# 04_-_CPU_SIGNALS.net
KiCad netlist of a schematic drawn in Altium Designer
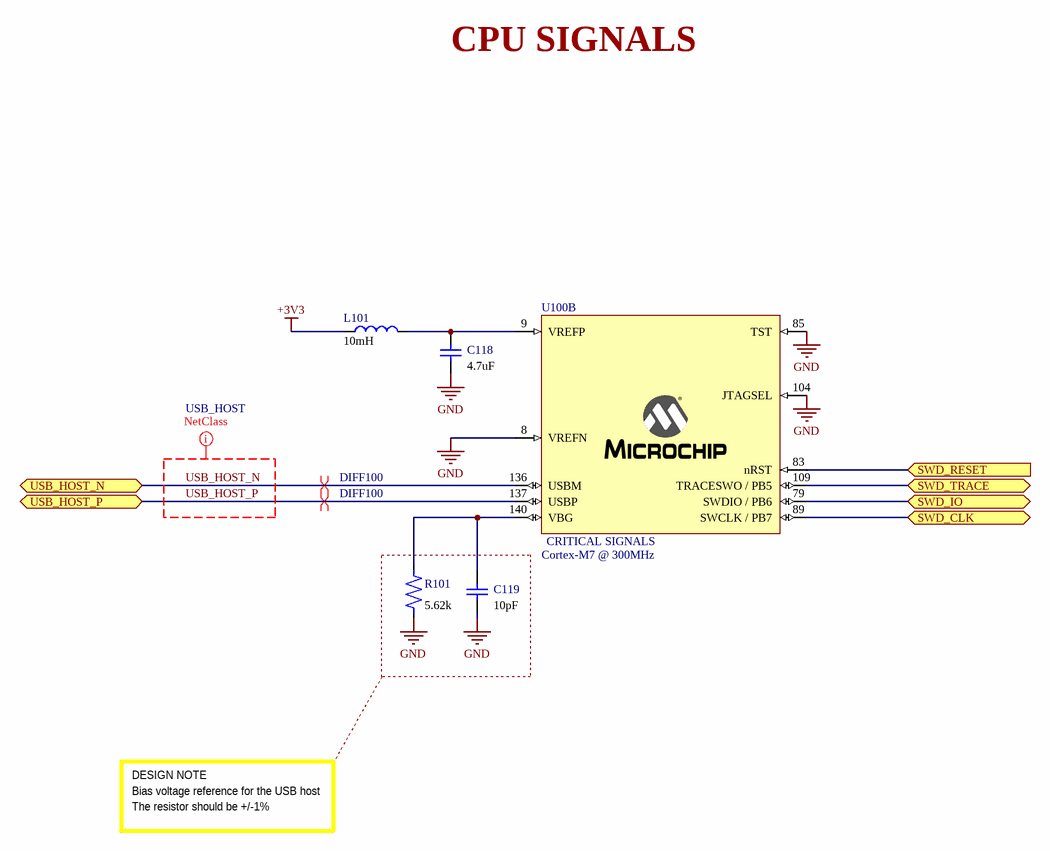
[diagram p0: [04] - CPU SIGNALS.SchDoc]

(export (version "E")
  (design (tool "Eeschema 10.0.6"))
  (components
    (comp (ref "C118")
      (value "4.7uF")
      (footprint "C0402")
      (description "C0402")
      (fields (field (name "Comment") "04023C103KAT2A"))
      (libsource (lib "Passive components") (part "04023C103KAT2A"))
    )
    (comp (ref "C119")
      (value "10pF")
      (footprint "C0402")
      (description "C0402")
      (fields (field (name "Comment") "04023C103KAT2A"))
      (libsource (lib "Passive components") (part "04023C103KAT2A"))
    )
    (comp (ref "L101")
      (value "10mH")
      (footprint "Inductor 0603")
      (description "Inductor 0603")
      (fields (field (name "Comment") "MLZ1608A2R2WT"))
      (libsource (lib "Passive components") (part "MLZ1608A2R2WT"))
    )
    (comp (ref "R101")
      (value "5.62k")
      (footprint "R0402")
      (description "R0402")
      (fields (field (name "Comment") "CRCW04020000Z0ED"))
      (libsource (lib "Passive components") (part "CRCW04020000Z0ED"))
    )
    (comp (ref "U100")
      (value "Cortex-M7 @ 300MHz")
      (footprint "ATSAMS70Q21A-AN")
      (description "ATSAMS70Q21")
      (libsource (lib "Microcontrollers") (part "ATSAMS70Q21A-AN"))
    )
  )
  (nets
    (net (code "1") (name "+3V3") (class "Default")
      (node (ref "L101") (pin "1") (pinfunction "1_1") (pintype "passive"))
    )
    (net (code "2") (name "/SWD_CLK") (class "Default")
      (node (ref "U100") (pin "89") (pinfunction "SWCLK_/_PB7_89") (pintype "bidirectional"))
    )
    (net (code "3") (name "/SWD_IO") (class "Default")
      (node (ref "U100") (pin "79") (pinfunction "SWDIO_/_PB6_79") (pintype "bidirectional"))
    )
    (net (code "4") (name "/SWD_RESET") (class "Default")
      (node (ref "U100") (pin "83") (pinfunction "nRST_83") (pintype "input"))
    )
    (net (code "5") (name "/SWD_TRACE") (class "Default")
      (node (ref "U100") (pin "109") (pinfunction "TRACESWO_/_PB5_109") (pintype "bidirectional"))
    )
    (net (code "6") (name "/USB_HOST_N") (class "Default")
      (node (ref "U100") (pin "136") (pinfunction "USBM_136") (pintype "bidirectional"))
    )
    (net (code "7") (name "/USB_HOST_P") (class "Default")
      (node (ref "U100") (pin "137") (pinfunction "USBP_137") (pintype "bidirectional"))
    )
    (net (code "8") (name "GND") (class "Default")
      (node (ref "C118") (pin "1") (pinfunction "1_1") (pintype "passive"))
      (node (ref "C119") (pin "1") (pinfunction "1_1") (pintype "passive"))
      (node (ref "R101") (pin "1") (pinfunction "1_1") (pintype "passive"))
      (node (ref "U100") (pin "104") (pinfunction "JTAGSEL_104") (pintype "input"))
      (node (ref "U100") (pin "8") (pinfunction "VREFN_8") (pintype "input"))
      (node (ref "U100") (pin "85") (pinfunction "TST_85") (pintype "input"))
    )
    (net (code "9") (name "Net-(R101-3)") (class "Default")
      (node (ref "C119") (pin "2") (pinfunction "2_2") (pintype "passive"))
      (node (ref "R101") (pin "2") (pinfunction "3_2") (pintype "passive"))
      (node (ref "U100") (pin "140") (pinfunction "VBG_140") (pintype "bidirectional"))
    )
    (net (code "10") (name "Net-(U100B-VREFP)") (class "Default")
      (node (ref "C118") (pin "2") (pinfunction "2_2") (pintype "passive"))
      (node (ref "L101") (pin "2") (pinfunction "2_2") (pintype "passive"))
      (node (ref "U100") (pin "9") (pinfunction "VREFP_9") (pintype "input"))
    )
  )
)
